# RAK3272.net
KiCad netlist of a schematic drawn in EAGLE
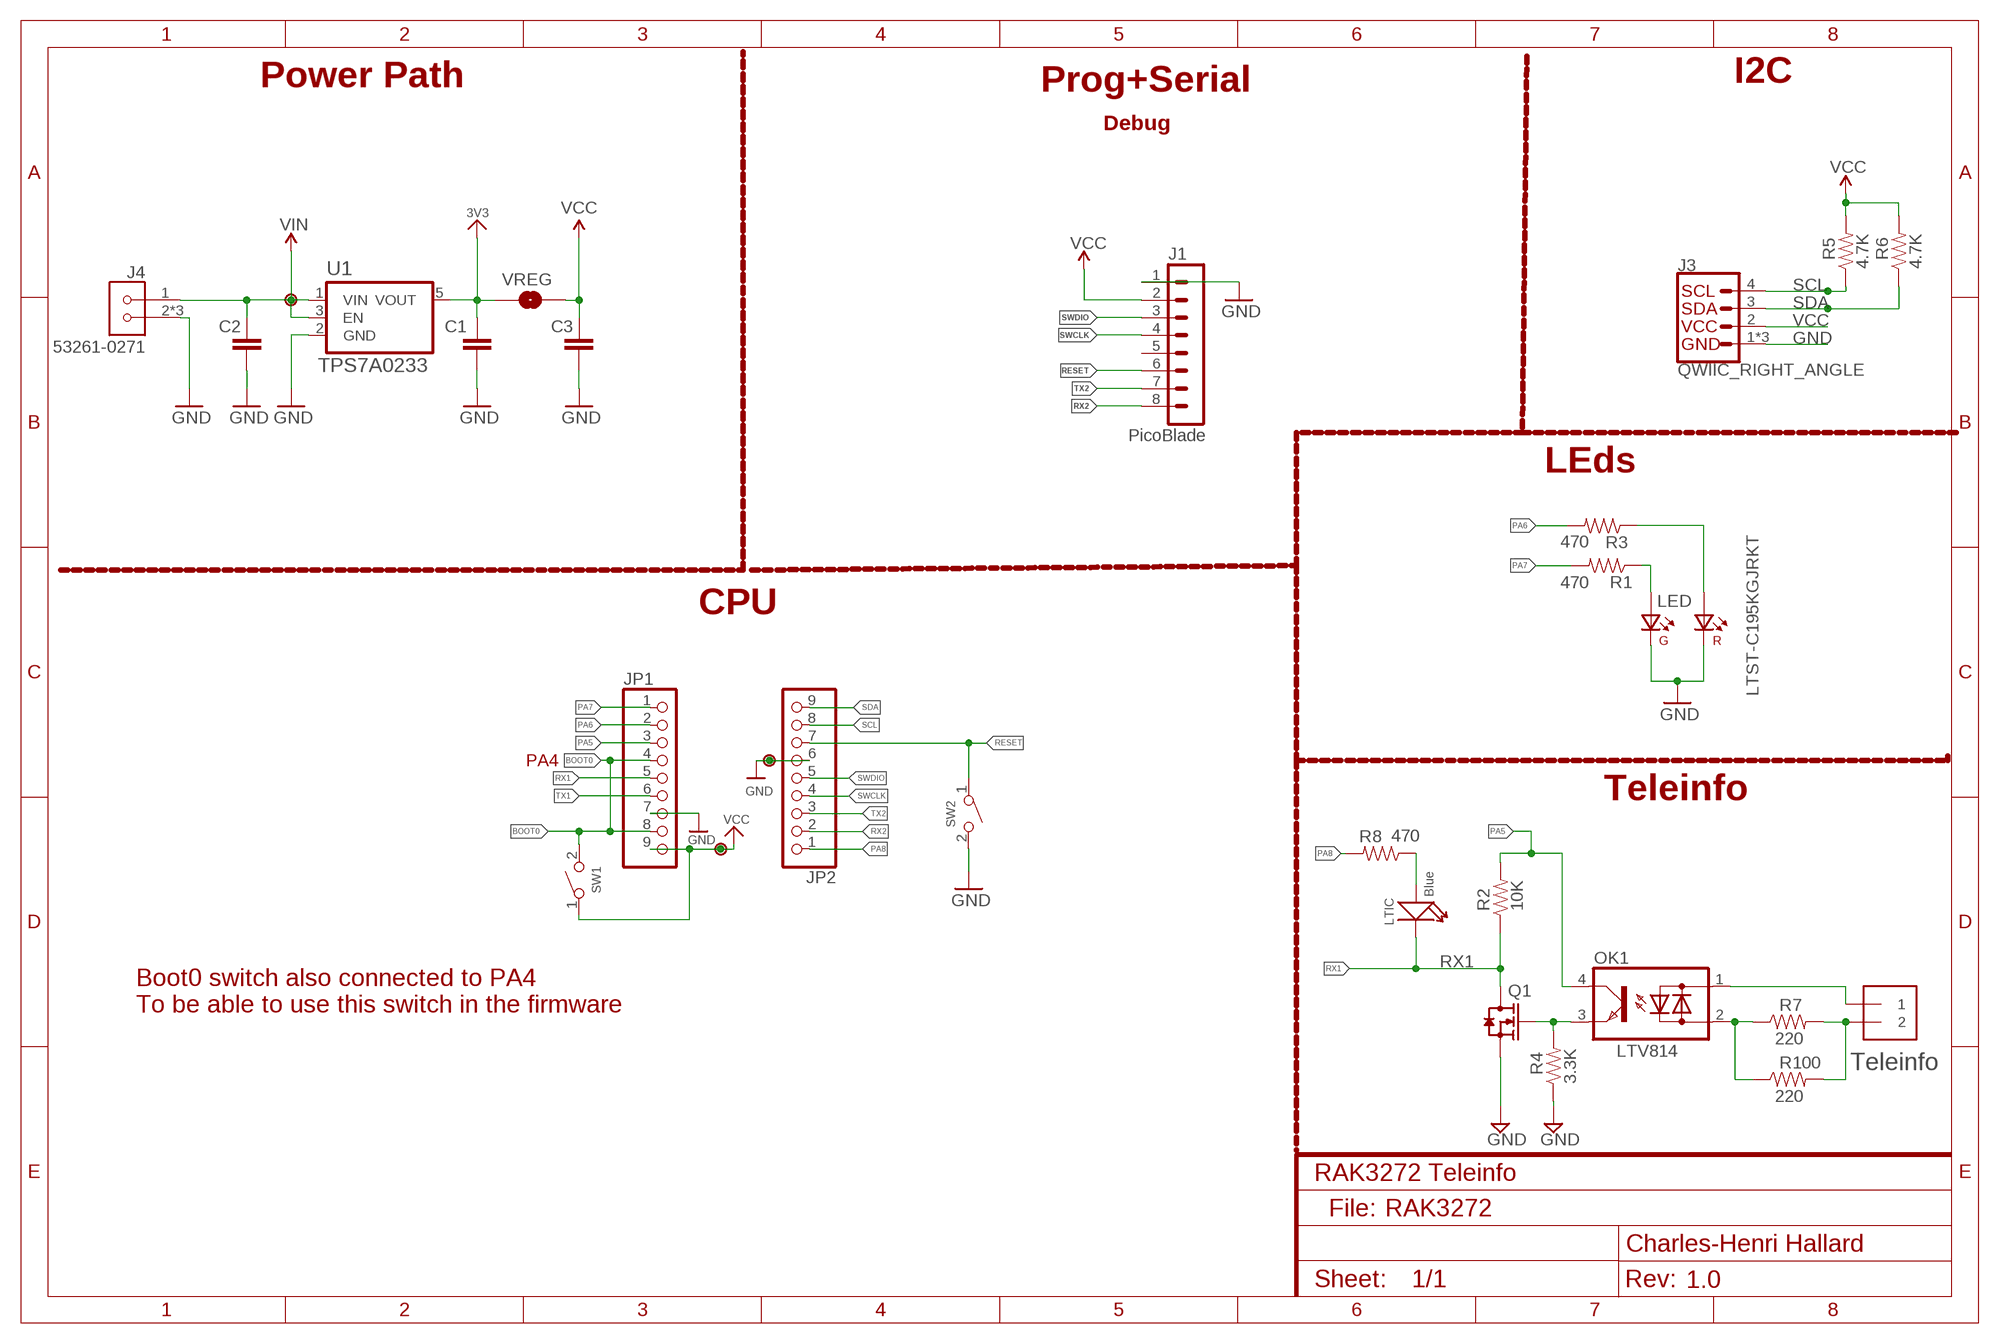
[diagram p0: schematic, sheet 1]

(export (version "E")
  (design (tool "Eeschema 10.0.6"))
  (components
    (comp (ref "C1")
      (value "1.0uF")
      (footprint "eagle-import:0402-CAP-OK")
      (libsource (lib "eagle-import") (part "CAP0402-CAP-OK"))
    )
    (comp (ref "C2")
      (value "1.0uF")
      (footprint "eagle-import:0402-CAP-OK")
      (libsource (lib "eagle-import") (part "CAP0402-CAP-OK"))
    )
    (comp (ref "C3")
      (value "1.0uF")
      (footprint "eagle-import:0402-CAP-OK")
      (libsource (lib "eagle-import") (part "CAP0402-CAP-OK"))
    )
    (comp (ref "J1")
      (value "PicoBlade")
      (footprint "eagle-import:53047-0810")
      (libsource (lib "eagle-import") (part "53047-0810"))
    )
    (comp (ref "J2")
      (value "1X2-3.5MM")
      (footprint "eagle-import:1X2-3.5MM")
      (libsource (lib "eagle-import") (part "1X2-3.5MM"))
    )
    (comp (ref "J3")
      (value "QWIIC_RIGHT_ANGLE")
      (footprint "eagle-import:JST04_1MM_HORI")
      (libsource (lib "eagle-import") (part "QWIIC_CONNECTOR_IICHORIZONTAL"))
    )
    (comp (ref "J4")
      (value "53261-0271")
      (footprint "eagle-import:MOLEX_53261-0271")
      (fields (field (name "MF") "Molex"))
      (libsource (lib "eagle-import") (part "53261-0271"))
    )
    (comp (ref "JP1")
      (value "PINHD-1X9")
      (footprint "eagle-import:1X09-BIG")
      (libsource (lib "eagle-import") (part "PINHD-1X9"))
    )
    (comp (ref "JP2")
      (value "PINHD-1X9")
      (footprint "eagle-import:1X09-BIG")
      (libsource (lib "eagle-import") (part "PINHD-1X9"))
    )
    (comp (ref "LED")
      (value "LTST-C195KGJRKT")
      (footprint "eagle-import:LTST-BILED-15X16")
      (fields (field (name "MF") "Lite-On Inc."))
      (libsource (lib "eagle-import") (part "LTST-C195KGJRKT"))
    )
    (comp (ref "LTIC")
      (value "Blue")
      (footprint "eagle-import:LED-0402")
      (fields (field (name "MPN") "BL-HB337A-AV-TRB"))
      (libsource (lib "eagle-import") (part "SMD-LED-CLEAR-BLUE(0402)"))
    )
    (comp (ref "OK1")
      (value "LTV814")
      (footprint "eagle-import:DIL4-SMD")
      (fields (field (name "MF") "VISHAY/TELEFUNKEN") (field (name "MPN") "SFH6206-3"))
      (libsource (lib "eagle-import") (part "SFH6206"))
    )
    (comp (ref "P1")
      (value "PADNORMAL")
      (footprint "eagle-import:PAD")
      (libsource (lib "eagle-import") (part "PADNORMAL"))
    )
    (comp (ref "P2")
      (value "PADNORMAL")
      (footprint "eagle-import:PAD")
      (libsource (lib "eagle-import") (part "PADNORMAL"))
    )
    (comp (ref "P3")
      (value "PADNORMAL")
      (footprint "eagle-import:PAD")
      (libsource (lib "eagle-import") (part "PADNORMAL"))
    )
    (comp (ref "Q1")
      (value "CJ2302")
      (footprint "eagle-import:SOT-323-3")
      (libsource (lib "eagle-import") (part "SMD-MOSFET-N-CH-20V-2.1A-CJ2302(SOT-23)"))
    )
    (comp (ref "R1")
      (value "470")
      (footprint "eagle-import:0402-RES")
      (libsource (lib "eagle-import") (part "RESISTOR0402-RES"))
    )
    (comp (ref "R2")
      (value "10K")
      (footprint "eagle-import:0402-RES")
      (libsource (lib "eagle-import") (part "RESISTOR0402-RES"))
    )
    (comp (ref "R3")
      (value "470")
      (footprint "eagle-import:0402-RES")
      (libsource (lib "eagle-import") (part "RESISTOR0402-RES"))
    )
    (comp (ref "R4")
      (value "3.3K")
      (footprint "eagle-import:0402-RES")
      (libsource (lib "eagle-import") (part "RESISTOR0402-RES"))
    )
    (comp (ref "R5")
      (value "4.7K")
      (footprint "eagle-import:0402-RES")
      (libsource (lib "eagle-import") (part "_c2h_RESISTOR0402-RES"))
    )
    (comp (ref "R6")
      (value "4.7K")
      (footprint "eagle-import:0402-RES")
      (libsource (lib "eagle-import") (part "_c2h_RESISTOR0402-RES"))
    )
    (comp (ref "R7")
      (value "220")
      (footprint "eagle-import:0402-RES")
      (libsource (lib "eagle-import") (part "_c2h_RESISTOR0402-RES"))
    )
    (comp (ref "R8")
      (value "470")
      (footprint "eagle-import:0402-RES")
      (libsource (lib "eagle-import") (part "RESISTOR0402-RES"))
    )
    (comp (ref "R100")
      (value "220")
      (footprint "eagle-import:1206")
      (libsource (lib "eagle-import") (part "_c2h_RESISTOR1206"))
    )
    (comp (ref "SW1")
      (value "B3U-1000P-2P-SMD")
      (footprint "eagle-import:C498294")
      (libsource (lib "eagle-import") (part "SMD-BUTTON(2P-3.0X2.5X1.2+0.4MM)"))
    )
    (comp (ref "SW2")
      (value "B3U-1000P-2P-SMD")
      (footprint "eagle-import:C498294")
      (libsource (lib "eagle-import") (part "SMD-BUTTON(2P-3.0X2.5X1.2+0.4MM)"))
    )
    (comp (ref "U1")
      (value "TPS7A0233")
      (footprint "eagle-import:SOT95P280X145-5N")
      (fields (field (name "MF") "Texas Instruments") (field (name "MP") "TPS7A0233PDBVR"))
      (libsource (lib "eagle-import") (part "TPS7A0233PDBVR"))
    )
    (comp (ref "VREG")
      (value "JUMPER-SMT_2_NO_NO-SILK")
      (footprint "eagle-import:SMT-JUMPER_2_NO_NO-SILK")
      (libsource (lib "eagle-import") (part "JUMPER-SMT_2_NO_NO-SILK"))
    )
  )
  (nets
    (net (code "1") (name "3V3") (class "Default")
      (node (ref "C1") (pin "1") (pinfunction "1_1") (pintype "passive"))
      (node (ref "U1") (pin "5") (pinfunction "VOUT_5") (pintype "output"))
      (node (ref "VREG") (pin "2") (pinfunction "2_2") (pintype "passive"))
    )
    (net (code "2") (name "BOOT0") (class "Default")
      (node (ref "JP1") (pin "4") (pinfunction "4_4") (pintype "passive"))
      (node (ref "JP1") (pin "8") (pinfunction "8_8") (pintype "passive"))
      (node (ref "SW1") (pin "2") (pinfunction "2_2") (pintype "bidirectional"))
    )
    (net (code "3") (name "GND") (class "Default")
      (node (ref "C1") (pin "2") (pinfunction "2_2") (pintype "passive"))
      (node (ref "C2") (pin "2") (pinfunction "2_2") (pintype "passive"))
      (node (ref "C3") (pin "2") (pinfunction "2_2") (pintype "passive"))
      (node (ref "J1") (pin "1") (pinfunction "1_1") (pintype "passive"))
      (node (ref "J3") (pin "1") (pinfunction "1_1") (pintype "power_in"))
      (node (ref "J3") (pin "NC1") (pinfunction "1_NC1") (pintype "power_in"))
      (node (ref "J3") (pin "NC2") (pinfunction "1_NC2") (pintype "power_in"))
      (node (ref "J4") (pin "2") (pinfunction "2_2") (pintype "passive"))
      (node (ref "J4") (pin "P1") (pinfunction "2_P1") (pintype "passive"))
      (node (ref "J4") (pin "P2") (pinfunction "2_P2") (pintype "passive"))
      (node (ref "JP1") (pin "7") (pinfunction "7_7") (pintype "passive"))
      (node (ref "JP2") (pin "6") (pinfunction "6_6") (pintype "passive"))
      (node (ref "LED") (pin "P$3") (pinfunction "K1_P$3") (pintype "passive"))
      (node (ref "LED") (pin "P$4") (pinfunction "K2_P$4") (pintype "passive"))
      (node (ref "P2") (pin "1") (pinfunction "1_1") (pintype "bidirectional"))
      (node (ref "Q1") (pin "2") (pinfunction "S_2") (pintype "passive"))
      (node (ref "R4") (pin "1") (pinfunction "1_1") (pintype "passive"))
      (node (ref "SW2") (pin "2") (pinfunction "2_2") (pintype "bidirectional"))
      (node (ref "U1") (pin "2") (pinfunction "GND_2") (pintype "power_in"))
    )
    (net (code "4") (name "Net-(J2-Pad2)") (class "Default")
      (node (ref "J2") (pin "2") (pinfunction "2_2") (pintype "passive"))
      (node (ref "R100") (pin "2") (pinfunction "2_2") (pintype "passive"))
      (node (ref "R7") (pin "2") (pinfunction "2_2") (pintype "passive"))
    )
    (net (code "5") (name "Net-(LED-A1)") (class "Default")
      (node (ref "LED") (pin "P$1") (pinfunction "A1_P$1") (pintype "passive"))
      (node (ref "R1") (pin "1") (pinfunction "1_1") (pintype "passive"))
    )
    (net (code "6") (name "Net-(LED-A2)") (class "Default")
      (node (ref "LED") (pin "P$2") (pinfunction "A2_P$2") (pintype "passive"))
      (node (ref "R3") (pin "1") (pinfunction "1_1") (pintype "passive"))
    )
    (net (code "7") (name "Net-(LTIC-Pad+)") (class "Default")
      (node (ref "LTIC") (pin "+") (pinfunction "+_+") (pintype "passive"))
      (node (ref "R8") (pin "1") (pinfunction "1_1") (pintype "passive"))
    )
    (net (code "8") (name "Net-(OK1-AC1)") (class "Default")
      (node (ref "J2") (pin "1") (pinfunction "1_1") (pintype "passive"))
      (node (ref "OK1") (pin "1") (pinfunction "AC1_1") (pintype "passive"))
    )
    (net (code "9") (name "Net-(OK1-AC2)") (class "Default")
      (node (ref "OK1") (pin "2") (pinfunction "AC2_2") (pintype "passive"))
      (node (ref "R100") (pin "1") (pinfunction "1_1") (pintype "passive"))
      (node (ref "R7") (pin "1") (pinfunction "1_1") (pintype "passive"))
    )
    (net (code "10") (name "Net-(OK1-E)") (class "Default")
      (node (ref "OK1") (pin "3") (pinfunction "E_3") (pintype "passive"))
      (node (ref "Q1") (pin "1") (pinfunction "G_1") (pintype "passive"))
      (node (ref "R4") (pin "2") (pinfunction "2_2") (pintype "passive"))
    )
    (net (code "11") (name "PA5") (class "Default")
      (node (ref "JP1") (pin "3") (pinfunction "3_3") (pintype "passive"))
      (node (ref "OK1") (pin "4") (pinfunction "C_4") (pintype "passive"))
      (node (ref "R2") (pin "2") (pinfunction "2_2") (pintype "passive"))
    )
    (net (code "12") (name "PA6") (class "Default")
      (node (ref "JP1") (pin "2") (pinfunction "2_2") (pintype "passive"))
      (node (ref "R3") (pin "2") (pinfunction "2_2") (pintype "passive"))
    )
    (net (code "13") (name "PA7") (class "Default")
      (node (ref "JP1") (pin "1") (pinfunction "1_1") (pintype "passive"))
      (node (ref "R1") (pin "2") (pinfunction "2_2") (pintype "passive"))
    )
    (net (code "14") (name "PA8") (class "Default")
      (node (ref "JP2") (pin "1") (pinfunction "1_1") (pintype "passive"))
      (node (ref "R8") (pin "2") (pinfunction "2_2") (pintype "passive"))
    )
    (net (code "15") (name "RESET") (class "Default")
      (node (ref "J1") (pin "6") (pinfunction "6_6") (pintype "passive"))
      (node (ref "JP2") (pin "7") (pinfunction "7_7") (pintype "passive"))
      (node (ref "SW2") (pin "1") (pinfunction "1_1") (pintype "bidirectional"))
    )
    (net (code "16") (name "RX1") (class "Default")
      (node (ref "JP1") (pin "5") (pinfunction "5_5") (pintype "passive"))
      (node (ref "LTIC") (pin "-") (pinfunction "-_-") (pintype "passive"))
      (node (ref "Q1") (pin "3") (pinfunction "D_3") (pintype "passive"))
      (node (ref "R2") (pin "1") (pinfunction "1_1") (pintype "passive"))
    )
    (net (code "17") (name "RX2") (class "Default")
      (node (ref "J1") (pin "8") (pinfunction "8_8") (pintype "passive"))
      (node (ref "JP2") (pin "2") (pinfunction "2_2") (pintype "passive"))
    )
    (net (code "18") (name "SCL") (class "Default")
      (node (ref "J3") (pin "4") (pinfunction "4_4") (pintype "passive"))
      (node (ref "JP2") (pin "8") (pinfunction "8_8") (pintype "passive"))
      (node (ref "R5") (pin "1") (pinfunction "1_1") (pintype "passive"))
    )
    (net (code "19") (name "SDA") (class "Default")
      (node (ref "J3") (pin "3") (pinfunction "3_3") (pintype "passive"))
      (node (ref "JP2") (pin "9") (pinfunction "9_9") (pintype "passive"))
      (node (ref "R6") (pin "1") (pinfunction "1_1") (pintype "passive"))
    )
    (net (code "20") (name "SWCLK") (class "Default")
      (node (ref "J1") (pin "4") (pinfunction "4_4") (pintype "passive"))
      (node (ref "JP2") (pin "4") (pinfunction "4_4") (pintype "passive"))
    )
    (net (code "21") (name "SWDIO") (class "Default")
      (node (ref "J1") (pin "3") (pinfunction "3_3") (pintype "passive"))
      (node (ref "JP2") (pin "5") (pinfunction "5_5") (pintype "passive"))
    )
    (net (code "22") (name "TX1") (class "Default")
      (node (ref "JP1") (pin "6") (pinfunction "6_6") (pintype "passive"))
    )
    (net (code "23") (name "TX2") (class "Default")
      (node (ref "J1") (pin "7") (pinfunction "7_7") (pintype "passive"))
      (node (ref "JP2") (pin "3") (pinfunction "3_3") (pintype "passive"))
    )
    (net (code "24") (name "VCC") (class "Default")
      (node (ref "C3") (pin "1") (pinfunction "1_1") (pintype "passive"))
      (node (ref "J1") (pin "2") (pinfunction "2_2") (pintype "passive"))
      (node (ref "J3") (pin "2") (pinfunction "2_2") (pintype "power_in"))
      (node (ref "JP1") (pin "9") (pinfunction "9_9") (pintype "passive"))
      (node (ref "P3") (pin "1") (pinfunction "1_1") (pintype "bidirectional"))
      (node (ref "R5") (pin "2") (pinfunction "2_2") (pintype "passive"))
      (node (ref "R6") (pin "2") (pinfunction "2_2") (pintype "passive"))
      (node (ref "SW1") (pin "1") (pinfunction "1_1") (pintype "bidirectional"))
      (node (ref "VREG") (pin "1") (pinfunction "1_1") (pintype "passive"))
    )
    (net (code "25") (name "VIN") (class "Default")
      (node (ref "C2") (pin "1") (pinfunction "1_1") (pintype "passive"))
      (node (ref "J4") (pin "1") (pinfunction "1_1") (pintype "passive"))
      (node (ref "P1") (pin "1") (pinfunction "1_1") (pintype "bidirectional"))
      (node (ref "U1") (pin "1") (pinfunction "VIN_1") (pintype "input"))
      (node (ref "U1") (pin "3") (pinfunction "EN_3") (pintype "input"))
    )
    (net (code "26") (name "unconnected-(J1-Pad5)") (class "Default")
      (node (ref "J1") (pin "5") (pinfunction "5_5") (pintype "passive"))
    )
  )
)
